# output_header.net
KiCad netlist of a schematic drawn in Altium Designer
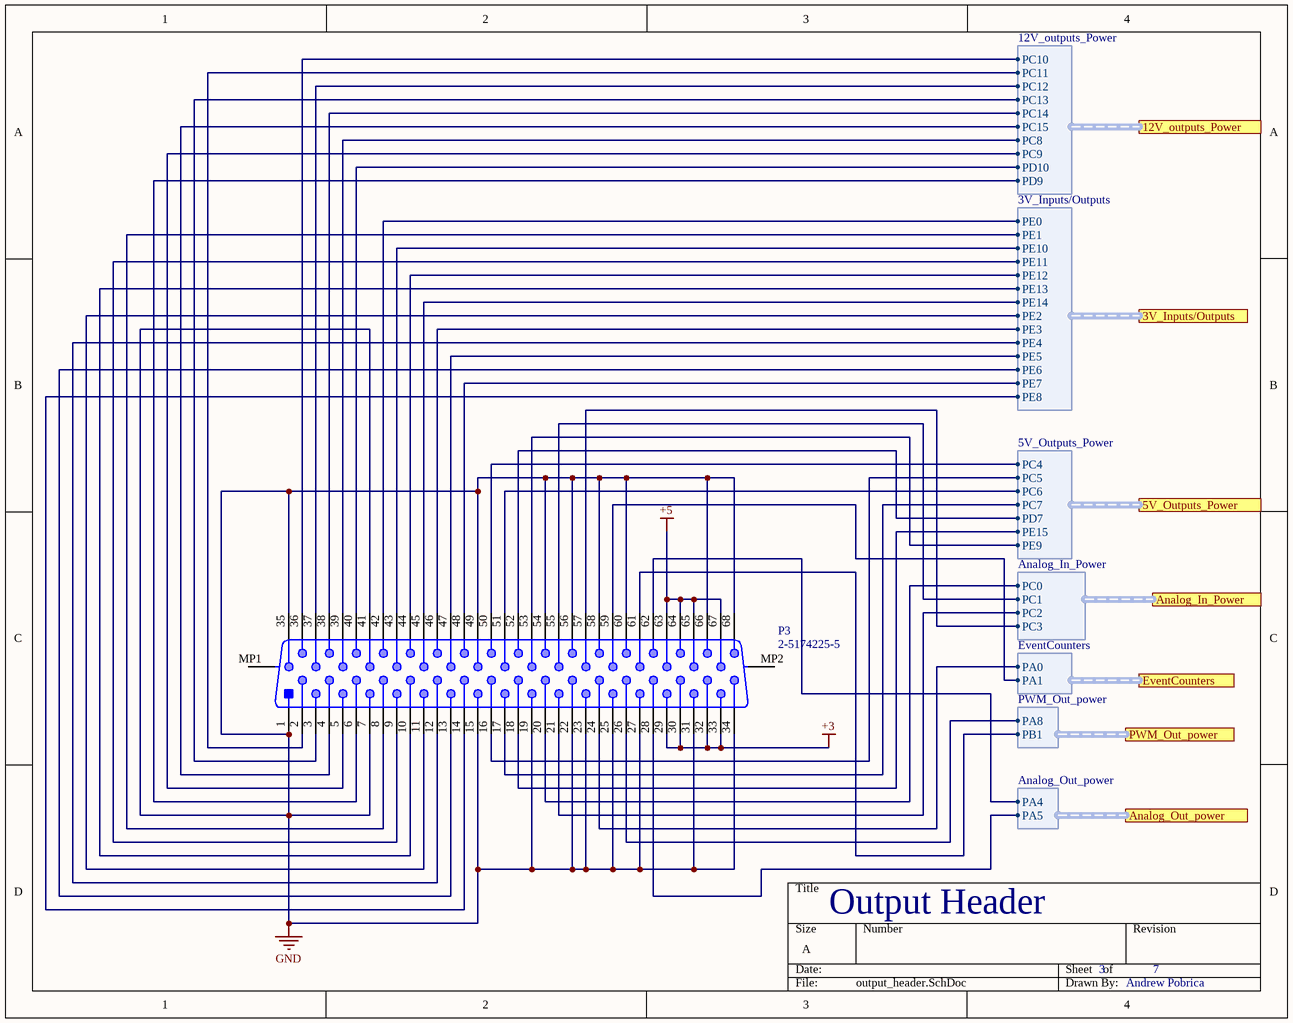
[diagram p0: output_header.SchDoc]

(export (version "E")
  (design (tool "Eeschema 10.0.6"))
  (components
    (comp (ref "P3")
      (value "2-5174225-5")
      (footprint "TECO-2-5174225-5-68_V")
      (fields (field (name "MANUFACTURER") "TE Connectivity"))
      (libsource (lib "Altium Content Vault") (part "CN-4S-2M-D68"))
    )
  )
  (nets
    (net (code "8") (name "+3") (class "Default")
      (node (ref "P3") (pin "29") (pinfunction "29_29") (pintype "passive"))
      (node (ref "P3") (pin "30") (pinfunction "30_30") (pintype "passive"))
      (node (ref "P3") (pin "32") (pinfunction "32_32") (pintype "passive"))
      (node (ref "P3") (pin "33") (pinfunction "33_33") (pintype "passive"))
    )
    (net (code "9") (name "+5") (class "Default")
      (node (ref "P3") (pin "63") (pinfunction "63_63") (pintype "passive"))
      (node (ref "P3") (pin "64") (pinfunction "64_64") (pintype "passive"))
      (node (ref "P3") (pin "65") (pinfunction "65_65") (pintype "passive"))
      (node (ref "P3") (pin "67") (pinfunction "67_67") (pintype "passive"))
    )
    (net (code "10") (name "/PA0") (class "Default")
      (node (ref "P3") (pin "24") (pinfunction "24_24") (pintype "passive"))
    )
    (net (code "11") (name "/PA1") (class "Default")
      (node (ref "P3") (pin "59") (pinfunction "59_59") (pintype "passive"))
    )
    (net (code "12") (name "/PA4") (class "Default")
      (node (ref "P3") (pin "62") (pinfunction "62_62") (pintype "passive"))
    )
    (net (code "13") (name "/PA5") (class "Default")
      (node (ref "P3") (pin "28") (pinfunction "28_28") (pintype "passive"))
    )
    (net (code "14") (name "/PA8") (class "Default")
      (node (ref "P3") (pin "26") (pinfunction "26_26") (pintype "passive"))
    )
    (net (code "15") (name "/PB1") (class "Default")
      (node (ref "P3") (pin "61") (pinfunction "61_61") (pintype "passive"))
    )
    (net (code "16") (name "/PC0") (class "Default")
      (node (ref "P3") (pin "20") (pinfunction "20_20") (pintype "passive"))
    )
    (net (code "17") (name "/PC1") (class "Default")
      (node (ref "P3") (pin "55") (pinfunction "55_55") (pintype "passive"))
    )
    (net (code "18") (name "/PC2") (class "Default")
      (node (ref "P3") (pin "21") (pinfunction "21_21") (pintype "passive"))
    )
    (net (code "19") (name "/PC3") (class "Default")
      (node (ref "P3") (pin "57") (pinfunction "57_57") (pintype "passive"))
    )
    (net (code "20") (name "/PC4") (class "Default")
      (node (ref "P3") (pin "50") (pinfunction "50_50") (pintype "passive"))
    )
    (net (code "21") (name "/PC5") (class "Default")
      (node (ref "P3") (pin "16") (pinfunction "16_16") (pintype "passive"))
    )
    (net (code "22") (name "/PC6") (class "Default")
      (node (ref "P3") (pin "51") (pinfunction "51_51") (pintype "passive"))
    )
    (net (code "23") (name "/PC7") (class "Default")
      (node (ref "P3") (pin "17") (pinfunction "17_17") (pintype "passive"))
    )
    (net (code "24") (name "/PC8") (class "Default")
      (node (ref "P3") (pin "39") (pinfunction "39_39") (pintype "passive"))
    )
    (net (code "25") (name "/PC9") (class "Default")
      (node (ref "P3") (pin "5") (pinfunction "5_5") (pintype "passive"))
    )
    (net (code "26") (name "/PC10") (class "Default")
      (node (ref "P3") (pin "36") (pinfunction "36_36") (pintype "passive"))
    )
    (net (code "27") (name "/PC11") (class "Default")
      (node (ref "P3") (pin "2") (pinfunction "2_2") (pintype "passive"))
    )
    (net (code "28") (name "/PC12") (class "Default")
      (node (ref "P3") (pin "37") (pinfunction "37_37") (pintype "passive"))
    )
    (net (code "29") (name "/PC13") (class "Default")
      (node (ref "P3") (pin "3") (pinfunction "3_3") (pintype "passive"))
    )
    (net (code "30") (name "/PC14") (class "Default")
      (node (ref "P3") (pin "38") (pinfunction "38_38") (pintype "passive"))
    )
    (net (code "31") (name "/PC15") (class "Default")
      (node (ref "P3") (pin "4") (pinfunction "4_4") (pintype "passive"))
    )
    (net (code "32") (name "/PD7") (class "Default")
      (node (ref "P3") (pin "52") (pinfunction "52_52") (pintype "passive"))
    )
    (net (code "33") (name "/PD9") (class "Default")
      (node (ref "P3") (pin "6") (pinfunction "6_6") (pintype "passive"))
    )
    (net (code "34") (name "/PD10") (class "Default")
      (node (ref "P3") (pin "40") (pinfunction "40_40") (pintype "passive"))
    )
    (net (code "35") (name "/PE0") (class "Default")
      (node (ref "P3") (pin "42") (pinfunction "42_42") (pintype "passive"))
    )
    (net (code "36") (name "/PE1") (class "Default")
      (node (ref "P3") (pin "8") (pinfunction "8_8") (pintype "passive"))
    )
    (net (code "37") (name "/PE2") (class "Default")
      (node (ref "P3") (pin "11") (pinfunction "11_11") (pintype "passive"))
    )
    (net (code "38") (name "/PE3") (class "Default")
      (node (ref "P3") (pin "46") (pinfunction "46_46") (pintype "passive"))
    )
    (net (code "39") (name "/PE4") (class "Default")
      (node (ref "P3") (pin "12") (pinfunction "12_12") (pintype "passive"))
    )
    (net (code "40") (name "/PE5") (class "Default")
      (node (ref "P3") (pin "47") (pinfunction "47_47") (pintype "passive"))
    )
    (net (code "41") (name "/PE6") (class "Default")
      (node (ref "P3") (pin "13") (pinfunction "13_13") (pintype "passive"))
    )
    (net (code "42") (name "/PE7") (class "Default")
      (node (ref "P3") (pin "48") (pinfunction "48_48") (pintype "passive"))
    )
    (net (code "43") (name "/PE8") (class "Default")
      (node (ref "P3") (pin "14") (pinfunction "14_14") (pintype "passive"))
    )
    (net (code "44") (name "/PE9") (class "Default")
      (node (ref "P3") (pin "53") (pinfunction "53_53") (pintype "passive"))
    )
    (net (code "45") (name "/PE10") (class "Default")
      (node (ref "P3") (pin "43") (pinfunction "43_43") (pintype "passive"))
    )
    (net (code "46") (name "/PE11") (class "Default")
      (node (ref "P3") (pin "9") (pinfunction "9_9") (pintype "passive"))
    )
    (net (code "47") (name "/PE12") (class "Default")
      (node (ref "P3") (pin "44") (pinfunction "44_44") (pintype "passive"))
    )
    (net (code "48") (name "/PE13") (class "Default")
      (node (ref "P3") (pin "10") (pinfunction "10_10") (pintype "passive"))
    )
    (net (code "49") (name "/PE14") (class "Default")
      (node (ref "P3") (pin "45") (pinfunction "45_45") (pintype "passive"))
    )
    (net (code "50") (name "/PE15") (class "Default")
      (node (ref "P3") (pin "18") (pinfunction "18_18") (pintype "passive"))
    )
    (net (code "58") (name "GND") (class "Default")
      (node (ref "P3") (pin "1") (pinfunction "1_1") (pintype "passive"))
      (node (ref "P3") (pin "15") (pinfunction "15_15") (pintype "passive"))
      (node (ref "P3") (pin "19") (pinfunction "19_19") (pintype "passive"))
      (node (ref "P3") (pin "22") (pinfunction "22_22") (pintype "passive"))
      (node (ref "P3") (pin "23") (pinfunction "23_23") (pintype "passive"))
      (node (ref "P3") (pin "25") (pinfunction "25_25") (pintype "passive"))
      (node (ref "P3") (pin "27") (pinfunction "27_27") (pintype "passive"))
      (node (ref "P3") (pin "31") (pinfunction "31_31") (pintype "passive"))
      (node (ref "P3") (pin "34") (pinfunction "34_34") (pintype "passive"))
      (node (ref "P3") (pin "35") (pinfunction "35_35") (pintype "passive"))
      (node (ref "P3") (pin "41") (pinfunction "41_41") (pintype "passive"))
      (node (ref "P3") (pin "49") (pinfunction "49_49") (pintype "passive"))
      (node (ref "P3") (pin "54") (pinfunction "54_54") (pintype "passive"))
      (node (ref "P3") (pin "56") (pinfunction "56_56") (pintype "passive"))
      (node (ref "P3") (pin "58") (pinfunction "58_58") (pintype "passive"))
      (node (ref "P3") (pin "60") (pinfunction "60_60") (pintype "passive"))
      (node (ref "P3") (pin "66") (pinfunction "66_66") (pintype "passive"))
      (node (ref "P3") (pin "68") (pinfunction "68_68") (pintype "passive"))
      (node (ref "P3") (pin "7") (pinfunction "7_7") (pintype "passive"))
    )
    (net (code "59") (name "unconnected-(P3-PadMP1)") (class "Default")
      (node (ref "P3") (pin "MP1") (pinfunction "MP1_MP1") (pintype "passive"))
    )
    (net (code "60") (name "unconnected-(P3-PadMP2)") (class "Default")
      (node (ref "P3") (pin "MP2") (pinfunction "MP2_MP2") (pintype "passive"))
    )
  )
)
